# Sheet1.net
KiCad netlist of a schematic drawn in Altium Designer
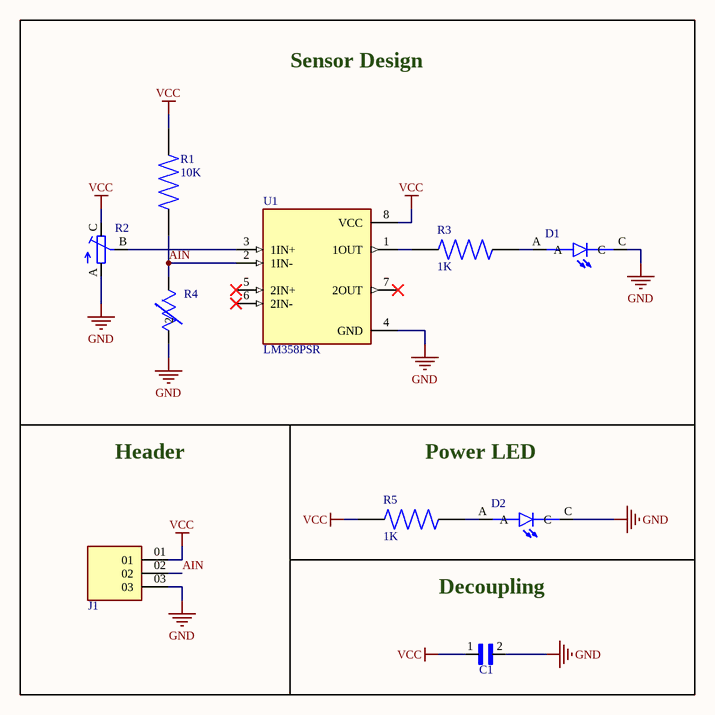
[diagram p0: Sheet1.SchDoc]

(export (version "E")
  (design (tool "Eeschema 10.0.6"))
  (components
    (comp (ref "C1")
      (value "CEU4J2X7R1H104K125AE")
      (footprint "CAPC2012X150N")
      (description "0.1 ÂµF Â±10% 50V Ceramic Capacitor X7R 0805 (2012 Metric)")
      (fields (field (name "MF") "TDK"))
      (libsource (lib "Schlib1") (part "CEU4J2X7R1H104K125AE"))
    )
    (comp (ref "D1")
      (value "597-3305-607F")
      (footprint "LEDC2012X70N")
      (description "LED Uni-Color Green 4-Pin Chip 0805 T/R")
      (libsource (lib "Schlib1") (part "597-3305-607F"))
    )
    (comp (ref "D2")
      (value "597-3305-607F")
      (footprint "LEDC2012X70N")
      (description "LED Uni-Color Green 4-Pin Chip 0805 T/R")
      (libsource (lib "Schlib1") (part "597-3305-607F"))
    )
    (comp (ref "J1")
      (value "MTLW-103-XX-XX-S-XXX")
      (footprint "SAMTEC_MTLW-103-XX-XX-S-XXX")
      (description "Connector Header Through Hole 40 position 0.100\" (2.54mm)")
      (libsource (lib "Schlib1") (part "MTLW-103-XX-XX-S-XXX"))
    )
    (comp (ref "R1")
      (value "10K")
      (footprint "RES_ERJU06J102V")
      (fields (field (name "MP") "ERJU06J102V"))
      (libsource (lib "Schlib1") (part "ERJU06J102V"))
    )
    (comp (ref "R2")
      (value "T93YA103KT20")
      (footprint "TRIM_T93YA103KT20")
      (description "10 kOhms 0.5W, 1/2W PC Pins Through Hole Trimmer Potentiometer Cermet 21.0 Turn Top Adjustment")
      (fields (field (name "MF") "Vishay"))
      (libsource (lib "Schlib1") (part "T93YA103KT20"))
    )
    (comp (ref "R3")
      (value "1K")
      (footprint "RES_ERJU06J102V")
      (fields (field (name "MP") "ERJU06J102V"))
      (libsource (lib "Schlib1") (part "ERJU06J102V"))
    )
    (comp (ref "R4")
      (value "MF52A1103F3380")
      (footprint "TRES_MF52-A_CTM")
      (description "THERMISTOR NTC 10KOHM 3380K BEAD")
      (fields (field (name "MF") "Cantherm"))
      (libsource (lib "Schlib1") (part "MF52A1103F3380"))
    )
    (comp (ref "R5")
      (value "1K")
      (footprint "RES_ERJU06J102V")
      (fields (field (name "MP") "ERJU06J102V"))
      (libsource (lib "Schlib1") (part "ERJU06J102V"))
    )
    (comp (ref "U1")
      (value "LM358PSR")
      (footprint "SOIC127P780X200-8N")
      (description "Dual, 30-V, 700-kHz operational amplifier")
      (fields (field (name "MF") "Texas Instruments"))
      (libsource (lib "Schlib1") (part "LM358PSR"))
    )
  )
  (nets
    (net (code "1") (name "/AIN") (class "Default")
      (node (ref "J1") (pin "02") (pinfunction "02_02") (pintype "passive"))
      (node (ref "R1") (pin "1") (pinfunction "1_1") (pintype "passive"))
      (node (ref "R4") (pin "1") (pinfunction "1_1") (pintype "passive"))
      (node (ref "U1") (pin "2") (pinfunction "1IN-_2") (pintype "input"))
    )
    (net (code "2") (name "GND") (class "Default")
      (node (ref "C1") (pin "2") (pinfunction "2_2") (pintype "passive"))
      (node (ref "D1") (pin "C") (pinfunction "C_C") (pintype "passive"))
      (node (ref "D2") (pin "C") (pinfunction "C_C") (pintype "passive"))
      (node (ref "J1") (pin "03") (pinfunction "03_03") (pintype "passive"))
      (node (ref "R2") (pin "A") (pinfunction "A_A") (pintype "passive"))
      (node (ref "R4") (pin "2") (pinfunction "2_2") (pintype "passive"))
      (node (ref "U1") (pin "4") (pinfunction "GND_4") (pintype "power_in"))
    )
    (net (code "3") (name "Net-(D1-PadA)") (class "Default")
      (node (ref "D1") (pin "A") (pinfunction "A_A") (pintype "passive"))
      (node (ref "R3") (pin "2") (pinfunction "2_2") (pintype "passive"))
    )
    (net (code "4") (name "Net-(D2-PadA)") (class "Default")
      (node (ref "D2") (pin "A") (pinfunction "A_A") (pintype "passive"))
      (node (ref "R5") (pin "2") (pinfunction "2_2") (pintype "passive"))
    )
    (net (code "5") (name "Net-(U1-1IN+)") (class "Default")
      (node (ref "R2") (pin "B") (pinfunction "B_B") (pintype "passive"))
      (node (ref "U1") (pin "3") (pinfunction "1IN+_3") (pintype "input"))
    )
    (net (code "6") (name "Net-(U1-1OUT)") (class "Default")
      (node (ref "R3") (pin "1") (pinfunction "1_1") (pintype "passive"))
      (node (ref "U1") (pin "1") (pinfunction "1OUT_1") (pintype "output"))
    )
    (net (code "7") (name "VCC") (class "Default")
      (node (ref "C1") (pin "1") (pinfunction "1_1") (pintype "passive"))
      (node (ref "J1") (pin "01") (pinfunction "01_01") (pintype "passive"))
      (node (ref "R1") (pin "2") (pinfunction "2_2") (pintype "passive"))
      (node (ref "R2") (pin "C") (pinfunction "C_C") (pintype "passive"))
      (node (ref "R5") (pin "1") (pinfunction "1_1") (pintype "passive"))
      (node (ref "U1") (pin "8") (pinfunction "VCC_8") (pintype "power_in"))
    )
    (net (code "8") (name "unconnected-(U1-2IN+-Pad5)") (class "Default")
      (node (ref "U1") (pin "5") (pinfunction "2IN+_5") (pintype "input+no_connect"))
    )
    (net (code "9") (name "unconnected-(U1-2IN--Pad6)") (class "Default")
      (node (ref "U1") (pin "6") (pinfunction "2IN-_6") (pintype "input+no_connect"))
    )
    (net (code "10") (name "unconnected-(U1-2OUT-Pad7)") (class "Default")
      (node (ref "U1") (pin "7") (pinfunction "2OUT_7") (pintype "output+no_connect"))
    )
  )
)
